# procesor_pot_display.net
KiCad netlist of a schematic drawn in EAGLE
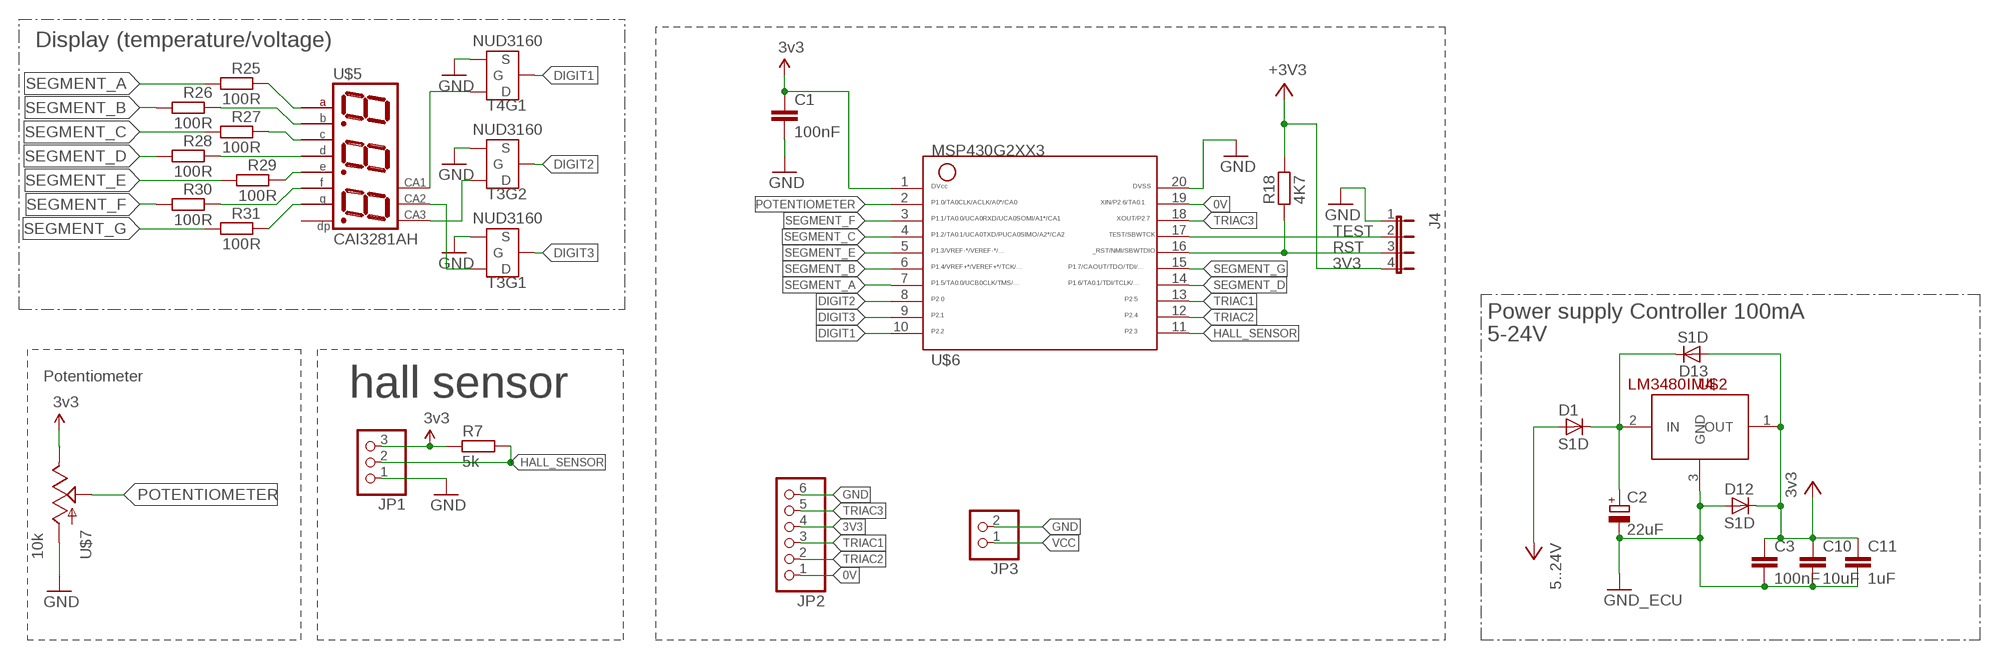
[diagram p0: schematic, sheet 1]

(export (version "E")
  (design (tool "Eeschema 10.0.6"))
  (components
    (comp (ref "C1")
      (value "100nF")
      (footprint "eagle-import:0603")
      (libsource (lib "eagle-import") (part "C0603"))
    )
    (comp (ref "C2")
      (value "22uF")
      (footprint "eagle-import:C_EL_6.3X5.4")
      (libsource (lib "eagle-import") (part "C_ELECTROLYTIC2"))
    )
    (comp (ref "C3")
      (value "100nF")
      (footprint "eagle-import:1206")
      (libsource (lib "eagle-import") (part "C1206"))
    )
    (comp (ref "C10")
      (value "10uF")
      (footprint "eagle-import:1206")
      (libsource (lib "eagle-import") (part "C1206"))
    )
    (comp (ref "C11")
      (value "1uF")
      (footprint "eagle-import:1206")
      (libsource (lib "eagle-import") (part "C1206"))
    )
    (comp (ref "D1")
      (value "S1D")
      (footprint "eagle-import:S1D")
      (libsource (lib "eagle-import") (part "DIODES1D"))
    )
    (comp (ref "D12")
      (value "S1D")
      (footprint "eagle-import:S1D")
      (libsource (lib "eagle-import") (part "DIODES1D"))
    )
    (comp (ref "D13")
      (value "S1D")
      (footprint "eagle-import:S1D")
      (libsource (lib "eagle-import") (part "DIODES1D"))
    )
    (comp (ref "J4")
      (value "JP4")
      (footprint "eagle-import:JP4")
      (libsource (lib "eagle-import") (part "JP4"))
    )
    (comp (ref "JP1")
      (value "PINHD-1X3")
      (footprint "eagle-import:1X03")
      (libsource (lib "eagle-import") (part "PINHD-1X3"))
    )
    (comp (ref "JP2")
      (value "PINHD-1X6/90")
      (footprint "eagle-import:1X06_90")
      (libsource (lib "eagle-import") (part "PINHD-1X6/90"))
    )
    (comp (ref "JP3")
      (value "PINHD-1X2/90")
      (footprint "eagle-import:1X02_90")
      (libsource (lib "eagle-import") (part "PINHD-1X2/90"))
    )
    (comp (ref "R7")
      (value "5k")
      (footprint "eagle-import:0603")
      (libsource (lib "eagle-import") (part "adi_v1.6_R0603"))
    )
    (comp (ref "R18")
      (value "4K7")
      (footprint "eagle-import:0805")
      (libsource (lib "eagle-import") (part "R0805"))
    )
    (comp (ref "R25")
      (value "100R")
      (footprint "eagle-import:R0603")
      (libsource (lib "eagle-import") (part "R-EU_R0603"))
    )
    (comp (ref "R26")
      (value "100R")
      (footprint "eagle-import:R0603")
      (libsource (lib "eagle-import") (part "R-EU_R0603"))
    )
    (comp (ref "R27")
      (value "100R")
      (footprint "eagle-import:R0603")
      (libsource (lib "eagle-import") (part "R-EU_R0603"))
    )
    (comp (ref "R28")
      (value "100R")
      (footprint "eagle-import:R0603")
      (libsource (lib "eagle-import") (part "R-EU_R0603"))
    )
    (comp (ref "R29")
      (value "100R")
      (footprint "eagle-import:R0603")
      (libsource (lib "eagle-import") (part "R-EU_R0603"))
    )
    (comp (ref "R30")
      (value "100R")
      (footprint "eagle-import:R0603")
      (libsource (lib "eagle-import") (part "R-EU_R0603"))
    )
    (comp (ref "R31")
      (value "100R")
      (footprint "eagle-import:R0603")
      (libsource (lib "eagle-import") (part "R-EU_R0603"))
    )
    (comp (ref "T3")
      (value "NUD3160")
      (footprint "eagle-import:SOT23-6")
      (libsource (lib "eagle-import") (part "NUD3160-DUALSOT23-6"))
    )
    (comp (ref "T4")
      (value "NUD3160")
      (footprint "eagle-import:SOT23-6")
      (libsource (lib "eagle-import") (part "NUD3160-DUALSOT23-6"))
    )
    (comp (ref "U$2")
      (value "LM3480IM4")
      (footprint "eagle-import:SOT23-3")
      (libsource (lib "eagle-import") (part "LM3480IM4"))
    )
    (comp (ref "U$5")
      (value "CAI3281AH")
      (footprint "eagle-import:7SEG_3DIGIT_10MMX30MM")
      (libsource (lib "eagle-import") (part "CAI3281AH"))
    )
    (comp (ref "U$6")
      (value "G2XX3---PW20")
      (footprint "eagle-import:PW20")
      (libsource (lib "eagle-import") (part "G2XX3---PW20"))
    )
    (comp (ref "U$7")
      (value "10k")
      (footprint "eagle-import:POT")
      (libsource (lib "eagle-import") (part "POT"))
    )
  )
  (nets
    (net (code "1") (name "/RST") (class "Default")
      (node (ref "J4") (pin "3") (pinfunction "3_3") (pintype "passive"))
      (node (ref "R18") (pin "1") (pinfunction "1_1") (pintype "passive"))
      (node (ref "U$6") (pin "16") (pinfunction "16_16") (pintype "bidirectional"))
    )
    (net (code "2") (name "/TEST") (class "Default")
      (node (ref "J4") (pin "2") (pinfunction "2_2") (pintype "passive"))
      (node (ref "U$6") (pin "17") (pinfunction "17_17") (pintype "bidirectional"))
    )
    (net (code "3") (name "0V") (class "Default")
      (node (ref "JP2") (pin "1") (pinfunction "1_1") (pintype "passive"))
      (node (ref "U$6") (pin "19") (pinfunction "19_19") (pintype "bidirectional"))
    )
    (net (code "4") (name "3V3") (class "Default")
      (node (ref "C1") (pin "1") (pinfunction "1_1") (pintype "passive"))
      (node (ref "C10") (pin "1") (pinfunction "1_1") (pintype "passive"))
      (node (ref "C11") (pin "1") (pinfunction "1_1") (pintype "passive"))
      (node (ref "C3") (pin "1") (pinfunction "1_1") (pintype "passive"))
      (node (ref "D12") (pin "C") (pinfunction "C_C") (pintype "passive"))
      (node (ref "D13") (pin "A") (pinfunction "A_A") (pintype "passive"))
      (node (ref "J4") (pin "4") (pinfunction "4_4") (pintype "passive"))
      (node (ref "JP1") (pin "3") (pinfunction "3_3") (pintype "passive"))
      (node (ref "JP2") (pin "4") (pinfunction "4_4") (pintype "passive"))
      (node (ref "R18") (pin "2") (pinfunction "2_2") (pintype "passive"))
      (node (ref "R7") (pin "1") (pinfunction "1_1") (pintype "passive"))
      (node (ref "U$2") (pin "1") (pinfunction "OUT_1") (pintype "bidirectional"))
      (node (ref "U$6") (pin "1") (pinfunction "1_1") (pintype "bidirectional"))
      (node (ref "U$7") (pin "E@2") (pinfunction "E_E@2") (pintype "passive"))
    )
    (net (code "5") (name "DIGIT1") (class "Default")
      (node (ref "T4") (pin "P$2") (pinfunction "G_P$2") (pintype "passive"))
      (node (ref "U$6") (pin "10") (pinfunction "10_10") (pintype "bidirectional"))
    )
    (net (code "6") (name "DIGIT2") (class "Default")
      (node (ref "T3") (pin "P$5") (pinfunction "G_P$5") (pintype "passive"))
      (node (ref "U$6") (pin "8") (pinfunction "8_8") (pintype "bidirectional"))
    )
    (net (code "7") (name "DIGIT3") (class "Default")
      (node (ref "T3") (pin "P$2") (pinfunction "G_P$2") (pintype "passive"))
      (node (ref "U$6") (pin "9") (pinfunction "9_9") (pintype "bidirectional"))
    )
    (net (code "8") (name "GND") (class "Default")
      (node (ref "C1") (pin "2") (pinfunction "2_2") (pintype "passive"))
      (node (ref "C10") (pin "2") (pinfunction "2_2") (pintype "passive"))
      (node (ref "C11") (pin "2") (pinfunction "2_2") (pintype "passive"))
      (node (ref "C2") (pin "-") (pinfunction "-_-") (pintype "passive"))
      (node (ref "C3") (pin "2") (pinfunction "2_2") (pintype "passive"))
      (node (ref "D12") (pin "A") (pinfunction "A_A") (pintype "passive"))
      (node (ref "J4") (pin "1") (pinfunction "1_1") (pintype "passive"))
      (node (ref "JP1") (pin "1") (pinfunction "1_1") (pintype "passive"))
      (node (ref "JP2") (pin "6") (pinfunction "6_6") (pintype "passive"))
      (node (ref "JP3") (pin "2") (pinfunction "2_2") (pintype "passive"))
      (node (ref "T3") (pin "P$1") (pinfunction "S_P$1") (pintype "passive"))
      (node (ref "T3") (pin "P$4") (pinfunction "S_P$4") (pintype "passive"))
      (node (ref "T4") (pin "P$1") (pinfunction "S_P$1") (pintype "passive"))
      (node (ref "U$2") (pin "3") (pinfunction "GND_3") (pintype "bidirectional"))
      (node (ref "U$6") (pin "20") (pinfunction "20_20") (pintype "bidirectional"))
      (node (ref "U$7") (pin "E@1") (pinfunction "A_E@1") (pintype "passive"))
    )
    (net (code "9") (name "HALL_SENSOR") (class "Default")
      (node (ref "JP1") (pin "2") (pinfunction "2_2") (pintype "passive"))
      (node (ref "R7") (pin "2") (pinfunction "2_2") (pintype "passive"))
      (node (ref "U$6") (pin "11") (pinfunction "11_11") (pintype "bidirectional"))
    )
    (net (code "10") (name "Net-(T3A-D)") (class "Default")
      (node (ref "T3") (pin "P$6") (pinfunction "D_P$6") (pintype "passive"))
      (node (ref "U$5") (pin "P$8") (pinfunction "CA_P$8") (pintype "passive"))
    )
    (net (code "11") (name "Net-(T3B-D)") (class "Default")
      (node (ref "T3") (pin "P$3") (pinfunction "D_P$3") (pintype "passive"))
      (node (ref "U$5") (pin "P$7") (pinfunction "CA_P$7") (pintype "passive"))
    )
    (net (code "12") (name "Net-(T4A-D)") (class "Default")
      (node (ref "T4") (pin "P$6") (pinfunction "D_P$6") (pintype "passive"))
      (node (ref "U$5") (pin "P$11") (pinfunction "CA_P$11") (pintype "passive"))
    )
    (net (code "13") (name "Net-(U$2-IN)") (class "Default")
      (node (ref "C2") (pin "+") (pinfunction "+_+") (pintype "passive"))
      (node (ref "D1") (pin "C") (pinfunction "C_C") (pintype "passive"))
      (node (ref "D13") (pin "C") (pinfunction "C_C") (pintype "passive"))
      (node (ref "U$2") (pin "2") (pinfunction "IN_2") (pintype "bidirectional"))
    )
    (net (code "14") (name "Net-(U$5-A)") (class "Default")
      (node (ref "R25") (pin "1") (pinfunction "1_1") (pintype "passive"))
      (node (ref "U$5") (pin "P$10") (pinfunction "A_P$10") (pintype "passive"))
    )
    (net (code "15") (name "Net-(U$5-B)") (class "Default")
      (node (ref "R26") (pin "1") (pinfunction "1_1") (pintype "passive"))
      (node (ref "U$5") (pin "P$6") (pinfunction "B_P$6") (pintype "passive"))
    )
    (net (code "16") (name "Net-(U$5-C)") (class "Default")
      (node (ref "R27") (pin "1") (pinfunction "1_1") (pintype "passive"))
      (node (ref "U$5") (pin "P$4") (pinfunction "C_P$4") (pintype "passive"))
    )
    (net (code "17") (name "Net-(U$5-D)") (class "Default")
      (node (ref "R28") (pin "1") (pinfunction "1_1") (pintype "passive"))
      (node (ref "U$5") (pin "P$2") (pinfunction "D_P$2") (pintype "passive"))
    )
    (net (code "18") (name "Net-(U$5-E)") (class "Default")
      (node (ref "R29") (pin "1") (pinfunction "1_1") (pintype "passive"))
      (node (ref "U$5") (pin "P$9") (pinfunction "E_P$9") (pintype "passive"))
    )
    (net (code "19") (name "Net-(U$5-F)") (class "Default")
      (node (ref "R30") (pin "1") (pinfunction "1_1") (pintype "passive"))
      (node (ref "U$5") (pin "P$5") (pinfunction "F_P$5") (pintype "passive"))
    )
    (net (code "20") (name "Net-(U$5-G)") (class "Default")
      (node (ref "R31") (pin "1") (pinfunction "1_1") (pintype "passive"))
      (node (ref "U$5") (pin "P$3") (pinfunction "G_P$3") (pintype "passive"))
    )
    (net (code "21") (name "POTENTIOMETER") (class "Default")
      (node (ref "U$6") (pin "2") (pinfunction "2_2") (pintype "bidirectional"))
      (node (ref "U$7") (pin "WAND") (pinfunction "S_WAND") (pintype "passive"))
    )
    (net (code "22") (name "SEGMENT_A") (class "Default")
      (node (ref "R25") (pin "2") (pinfunction "2_2") (pintype "passive"))
      (node (ref "U$6") (pin "7") (pinfunction "7_7") (pintype "bidirectional"))
    )
    (net (code "23") (name "SEGMENT_B") (class "Default")
      (node (ref "R26") (pin "2") (pinfunction "2_2") (pintype "passive"))
      (node (ref "U$6") (pin "6") (pinfunction "6_6") (pintype "bidirectional"))
    )
    (net (code "24") (name "SEGMENT_C") (class "Default")
      (node (ref "R27") (pin "2") (pinfunction "2_2") (pintype "passive"))
      (node (ref "U$6") (pin "4") (pinfunction "4_4") (pintype "bidirectional"))
    )
    (net (code "25") (name "SEGMENT_D") (class "Default")
      (node (ref "R28") (pin "2") (pinfunction "2_2") (pintype "passive"))
      (node (ref "U$6") (pin "14") (pinfunction "14_14") (pintype "bidirectional"))
    )
    (net (code "26") (name "SEGMENT_E") (class "Default")
      (node (ref "R29") (pin "2") (pinfunction "2_2") (pintype "passive"))
      (node (ref "U$6") (pin "5") (pinfunction "5_5") (pintype "bidirectional"))
    )
    (net (code "27") (name "SEGMENT_F") (class "Default")
      (node (ref "R30") (pin "2") (pinfunction "2_2") (pintype "passive"))
      (node (ref "U$6") (pin "3") (pinfunction "3_3") (pintype "bidirectional"))
    )
    (net (code "28") (name "SEGMENT_G") (class "Default")
      (node (ref "R31") (pin "2") (pinfunction "2_2") (pintype "passive"))
      (node (ref "U$6") (pin "15") (pinfunction "15_15") (pintype "bidirectional"))
    )
    (net (code "29") (name "TRIAC1") (class "Default")
      (node (ref "JP2") (pin "3") (pinfunction "3_3") (pintype "passive"))
      (node (ref "U$6") (pin "13") (pinfunction "13_13") (pintype "bidirectional"))
    )
    (net (code "30") (name "TRIAC2") (class "Default")
      (node (ref "JP2") (pin "2") (pinfunction "2_2") (pintype "passive"))
      (node (ref "U$6") (pin "12") (pinfunction "12_12") (pintype "bidirectional"))
    )
    (net (code "31") (name "TRIAC3") (class "Default")
      (node (ref "JP2") (pin "5") (pinfunction "5_5") (pintype "passive"))
      (node (ref "U$6") (pin "18") (pinfunction "18_18") (pintype "bidirectional"))
    )
    (net (code "32") (name "VCC") (class "Default")
      (node (ref "D1") (pin "A") (pinfunction "A_A") (pintype "passive"))
      (node (ref "JP3") (pin "1") (pinfunction "1_1") (pintype "passive"))
    )
    (net (code "33") (name "unconnected-(U$5-DP-PadP$1)") (class "Default")
      (node (ref "U$5") (pin "P$1") (pinfunction "DP_P$1") (pintype "passive"))
    )
  )
)
